# filter-9.net
KiCad netlist of a schematic drawn in Altium Designer
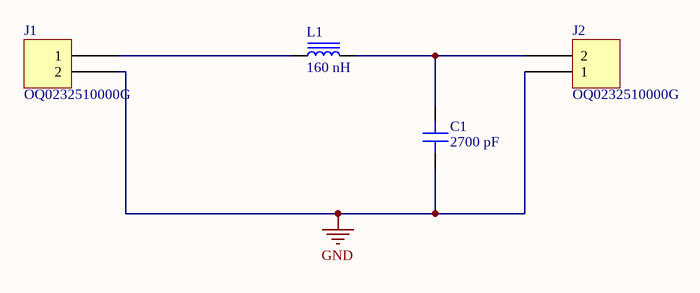
[diagram p0: filter-9.SchDoc]

(export (version "E")
  (design (tool "Eeschema 10.0.6"))
  (components
    (comp (ref "C1")
      (value "2700 pF")
      (footprint "CAP 0603_1608")
      (description "CAP CER 2700PF 25V NP0 0603")
      (fields (field (name "PART NUMBER") "C0603C272F3GAC7867") (field (name "MANUFACTURER") "KEMET"))
      (libsource (lib "Celestial Altium Library - altium_library") (part "Capacitor"))
    )
    (comp (ref "J1")
      (value "OQ0232510000G")
      (footprint "FCI 06-381-2PIN")
      (description "TERM BLOCK HDR 2POS 90DEG 3.81MM")
      (fields (field (name "MANUFACTURER") "Amphenol Anytek"))
      (libsource (lib "Celestial Altium Library - altium_library") (part "2 Pin"))
    )
    (comp (ref "J2")
      (value "OQ0232510000G")
      (footprint "FCI 06-381-2PIN")
      (description "TERM BLOCK HDR 2POS 90DEG 3.81MM")
      (fields (field (name "MANUFACTURER") "Amphenol Anytek"))
      (libsource (lib "") (part "2 Pin_1"))
    )
    (comp (ref "L1")
      (value "160 nH")
      (footprint "IND 0402_1005 RF WW")
      (description "FIXED IND 160NH 480MA 330MOHM SM")
      (fields
        (field (name "PART NUMBER") "LQW15CNR16J00D")
        (field (name "MANUFACTURER") "Murata Electronics")
      )
      (libsource (lib "Celestial Altium Library - altium_library") (part "Inductor"))
    )
  )
  (nets
    (net (code "1") (name "GND") (class "Default")
      (node (ref "C1") (pin "1") (pinfunction "1_1") (pintype "passive"))
      (node (ref "J1") (pin "2") (pinfunction "2_2") (pintype "passive"))
      (node (ref "J2") (pin "1") (pinfunction "1_1") (pintype "passive"))
    )
    (net (code "2") (name "Net-(C1-Pad2)") (class "Default")
      (node (ref "C1") (pin "2") (pinfunction "2_2") (pintype "passive"))
      (node (ref "J2") (pin "2") (pinfunction "2_2") (pintype "passive"))
      (node (ref "L1") (pin "2") (pinfunction "2_2") (pintype "passive"))
    )
    (net (code "3") (name "Net-(J1-Pad1)") (class "Default")
      (node (ref "J1") (pin "1") (pinfunction "1_1") (pintype "passive"))
      (node (ref "L1") (pin "1") (pinfunction "1_1") (pintype "passive"))
    )
  )
)
